# treiber.net
KiCad netlist of a schematic drawn in EAGLE
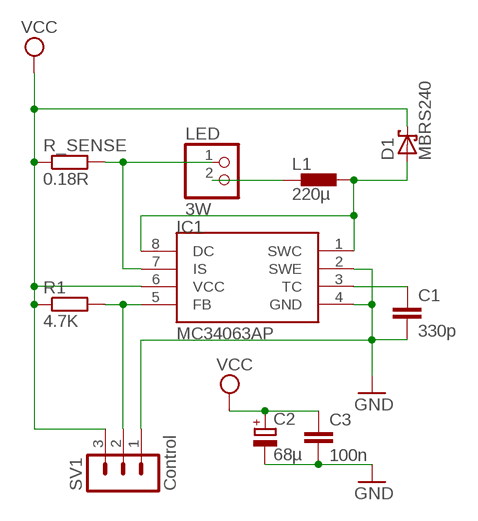
[diagram p0: schematic, sheet 1]

(export (version "E")
  (design (tool "Eeschema 10.0.6"))
  (components
    (comp (ref "C1")
      (value "330p")
      (footprint "eagle-import:C050-024X044")
      (libsource (lib "eagle-import") (part "C-EU050-024X044"))
    )
    (comp (ref "C2")
      (value "68µ")
      (footprint "eagle-import:E2,5-5")
      (libsource (lib "eagle-import") (part "CPOL-EUE2.5-5"))
    )
    (comp (ref "C3")
      (value "100n")
      (footprint "eagle-import:C5B2.5")
      (libsource (lib "eagle-import") (part "C5/2.5"))
    )
    (comp (ref "D1")
      (value "MBRS240")
      (footprint "eagle-import:DO35-7")
      (libsource (lib "eagle-import") (part "SCHOTTKY-DIODEDO35-7"))
    )
    (comp (ref "IC1")
      (value "MC34063AP")
      (footprint "eagle-import:DIL08")
      (libsource (lib "eagle-import") (part "MC34063AP"))
    )
    (comp (ref "L1")
      (value "220µ")
      (footprint "eagle-import:DR1030")
      (libsource (lib "eagle-import") (part "DR1030"))
    )
    (comp (ref "LED")
      (value "3W")
      (footprint "eagle-import:1X02")
      (libsource (lib "eagle-import") (part "PINHD-1X2"))
    )
    (comp (ref "R1")
      (value "4.7K")
      (footprint "eagle-import:0207_10")
      (libsource (lib "eagle-import") (part "R-EU_0207/10"))
    )
    (comp (ref "R_SENSE")
      (value "0.18R")
      (footprint "eagle-import:0411_15")
      (libsource (lib "eagle-import") (part "R-EU_0411/15"))
    )
    (comp (ref "SV1")
      (value "Control")
      (footprint "eagle-import:MA03-1")
      (libsource (lib "eagle-import") (part "MA03-1"))
    )
  )
  (nets
    (net (code "1") (name "GND") (class "Default")
      (node (ref "C1") (pin "2") (pinfunction "2_2") (pintype "passive"))
      (node (ref "C2") (pin "-") (pinfunction "-_-") (pintype "passive"))
      (node (ref "C3") (pin "2") (pinfunction "2_2") (pintype "passive"))
      (node (ref "IC1") (pin "2") (pinfunction "SWE_2") (pintype "passive"))
      (node (ref "IC1") (pin "4") (pinfunction "GND_4") (pintype "passive"))
      (node (ref "SV1") (pin "1") (pinfunction "1_1") (pintype "passive"))
    )
    (net (code "2") (name "Net-(IC1-DC)") (class "Default")
      (node (ref "D1") (pin "A") (pinfunction "A_A") (pintype "passive"))
      (node (ref "IC1") (pin "1") (pinfunction "SWC_1") (pintype "passive"))
      (node (ref "IC1") (pin "8") (pinfunction "DC_8") (pintype "passive"))
      (node (ref "L1") (pin "2") (pinfunction "2_2") (pintype "passive"))
    )
    (net (code "3") (name "Net-(IC1-FB)") (class "Default")
      (node (ref "IC1") (pin "5") (pinfunction "FB_5") (pintype "passive"))
      (node (ref "R1") (pin "2") (pinfunction "2_2") (pintype "passive"))
      (node (ref "SV1") (pin "2") (pinfunction "2_2") (pintype "passive"))
    )
    (net (code "4") (name "Net-(IC1-IS)") (class "Default")
      (node (ref "IC1") (pin "7") (pinfunction "IS_7") (pintype "passive"))
      (node (ref "LED") (pin "1") (pinfunction "1_1") (pintype "passive"))
      (node (ref "R_SENSE") (pin "2") (pinfunction "2_2") (pintype "passive"))
    )
    (net (code "5") (name "Net-(IC1-TC)") (class "Default")
      (node (ref "C1") (pin "1") (pinfunction "1_1") (pintype "passive"))
      (node (ref "IC1") (pin "3") (pinfunction "TC_3") (pintype "passive"))
    )
    (net (code "6") (name "Net-(L1-Pad1)") (class "Default")
      (node (ref "L1") (pin "1") (pinfunction "1_1") (pintype "passive"))
      (node (ref "LED") (pin "2") (pinfunction "2_2") (pintype "passive"))
    )
    (net (code "7") (name "VCC") (class "Default")
      (node (ref "C2") (pin "+") (pinfunction "+_+") (pintype "passive"))
      (node (ref "C3") (pin "1") (pinfunction "1_1") (pintype "passive"))
      (node (ref "D1") (pin "C") (pinfunction "C_C") (pintype "passive"))
      (node (ref "IC1") (pin "6") (pinfunction "VCC_6") (pintype "passive"))
      (node (ref "R1") (pin "1") (pinfunction "1_1") (pintype "passive"))
      (node (ref "R_SENSE") (pin "1") (pinfunction "1_1") (pintype "passive"))
      (node (ref "SV1") (pin "3") (pinfunction "3_3") (pintype "passive"))
    )
  )
)
